# Node.net
KiCad netlist of a schematic drawn in EAGLE
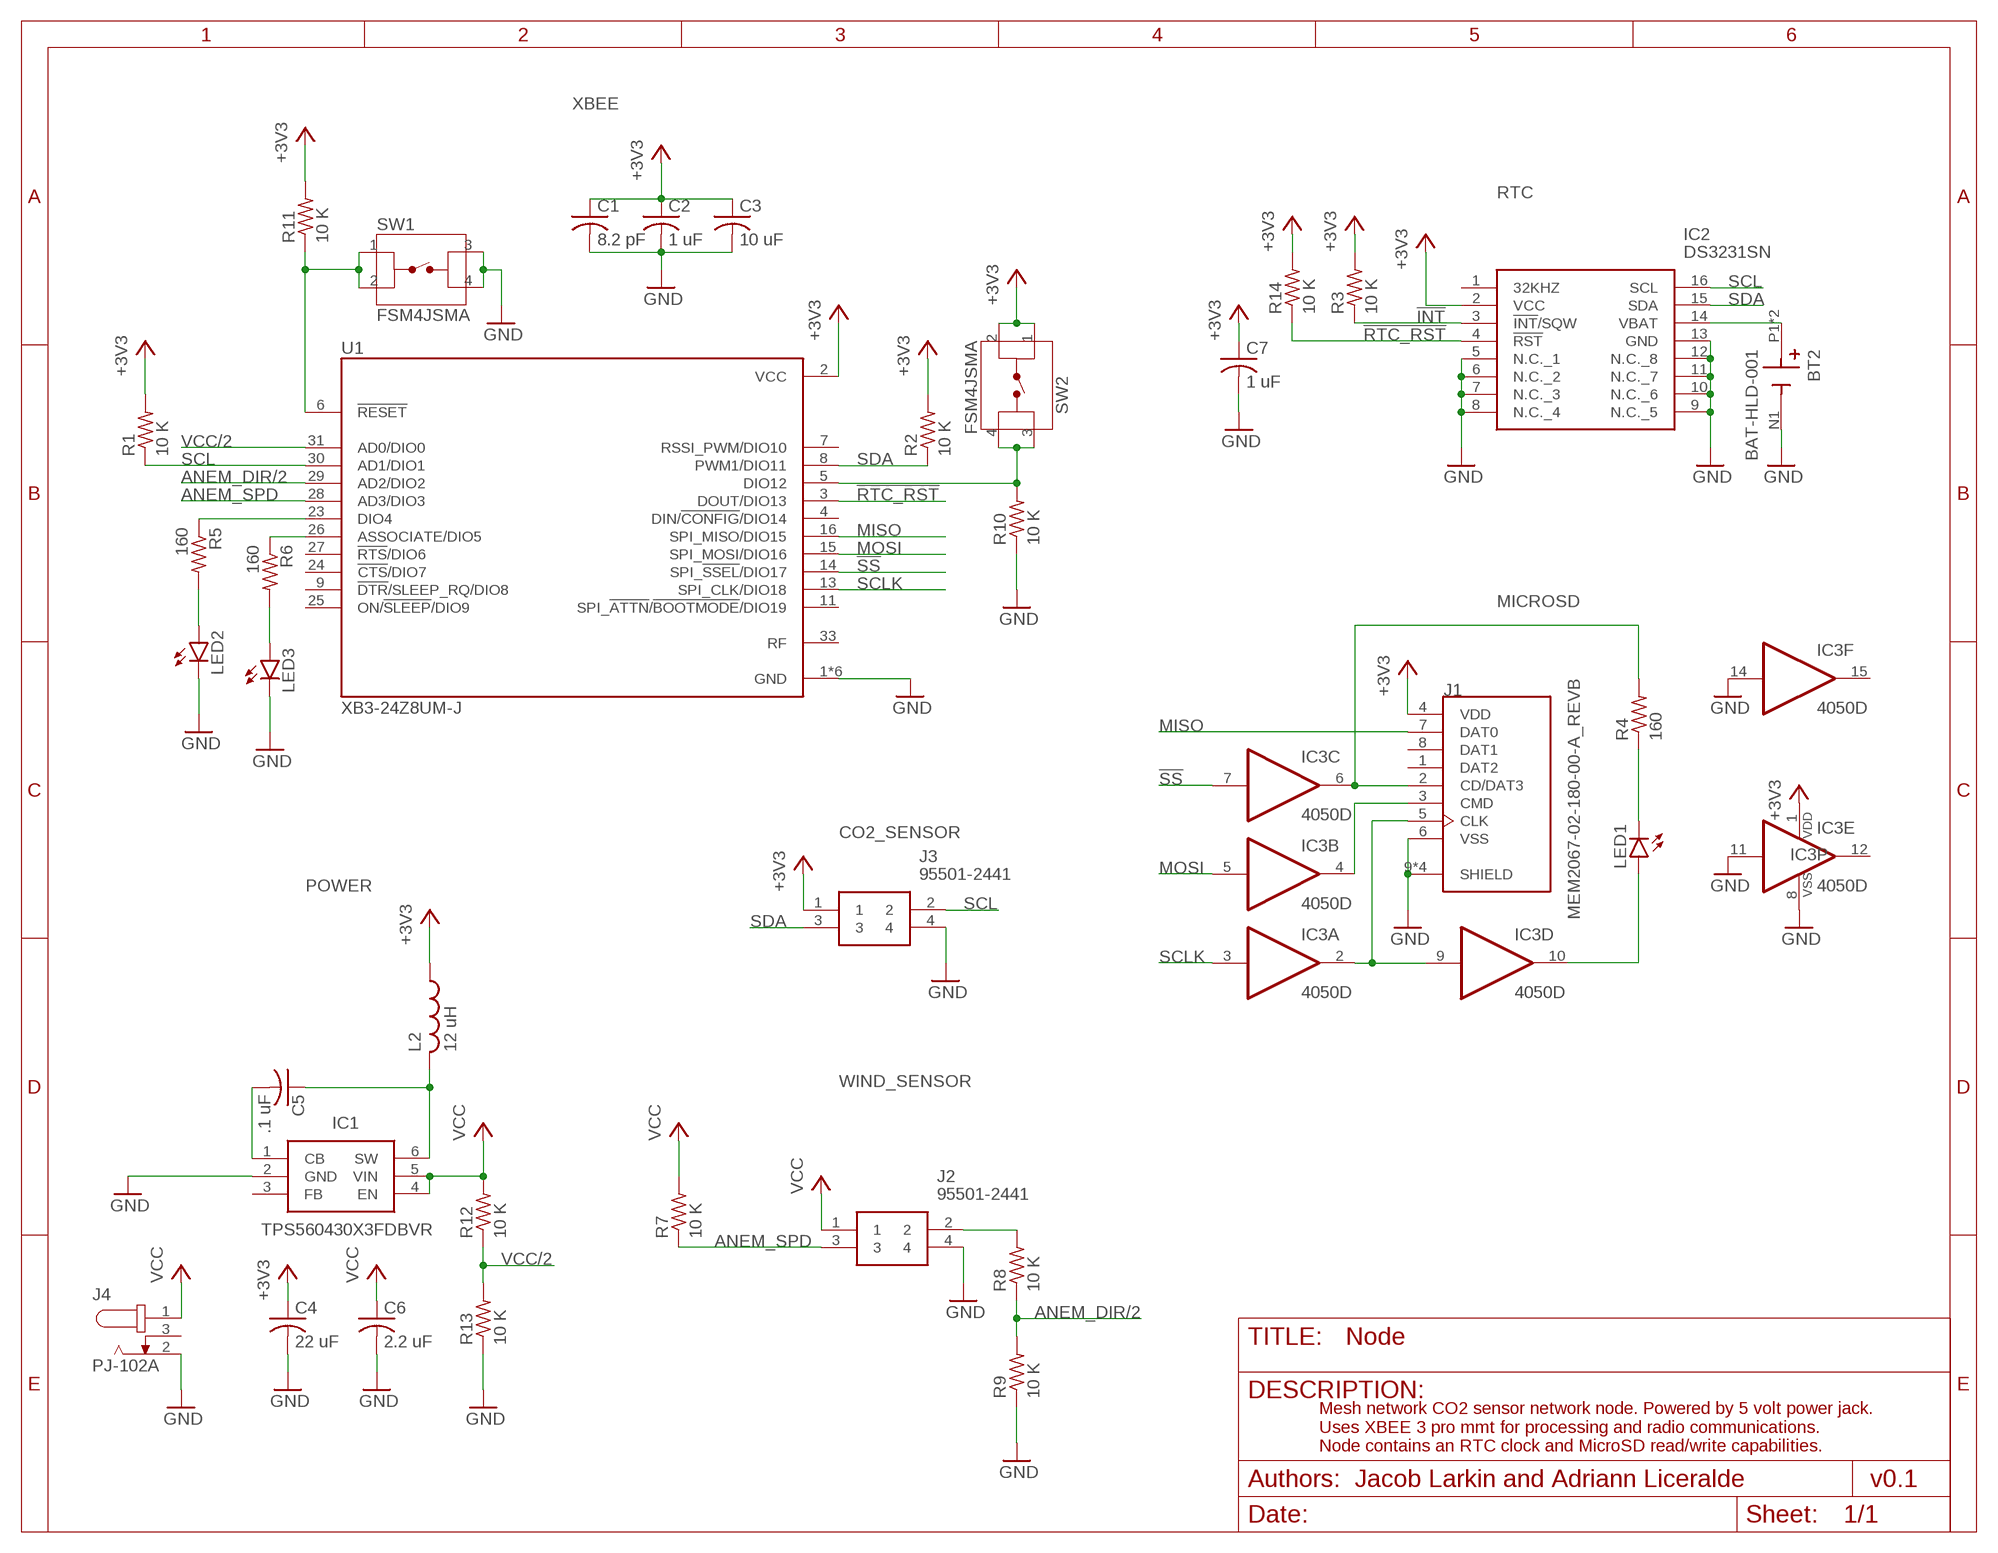
[diagram p0: schematic, sheet 1]

(export (version "E")
  (design (tool "Eeschema 10.0.6"))
  (components
    (comp (ref "BT2")
      (value "BAT-HLD-001")
      (footprint "eagle-import:BAT_BAT-HLD-001")
      (fields (field (name "MF") "Linx Technologies") (field (name "PRICE") ".29"))
      (libsource (lib "eagle-import") (part "BAT-HLD-001"))
    )
    (comp (ref "C1")
      (value "8.2 pF")
      (footprint "eagle-import:C0805")
      (libsource (lib "eagle-import") (part "C-USC0805"))
    )
    (comp (ref "C2")
      (value "1 uF")
      (footprint "eagle-import:C0805")
      (libsource (lib "eagle-import") (part "C-USC0805"))
    )
    (comp (ref "C3")
      (value "10 uF")
      (footprint "eagle-import:C0805")
      (libsource (lib "eagle-import") (part "C-USC0805"))
    )
    (comp (ref "C4")
      (value "22 uF")
      (footprint "eagle-import:C0805")
      (libsource (lib "eagle-import") (part "C-USC0805"))
    )
    (comp (ref "C5")
      (value ".1 uF")
      (footprint "eagle-import:C0805")
      (libsource (lib "eagle-import") (part "C-USC0805"))
    )
    (comp (ref "C6")
      (value "2.2 uF")
      (footprint "eagle-import:C0805")
      (libsource (lib "eagle-import") (part "C-USC0805"))
    )
    (comp (ref "C7")
      (value "1 uF")
      (footprint "eagle-import:C0805")
      (libsource (lib "eagle-import") (part "C-USC0805"))
    )
    (comp (ref "IC1")
      (value "TPS560430X3FDBVR")
      (footprint "eagle-import:SOT95P280X145-6N")
      (fields (field (name "MOUSER_PART_NUMBER") "595-TPS560430X3FDBVR"))
      (libsource (lib "eagle-import") (part "TPS560430X3FDBVR"))
    )
    (comp (ref "IC2")
      (value "DS3231SN")
      (footprint "eagle-import:SOIC127P1032X265-16N")
      (fields (field (name "MOUSER_PART_NUMBER") "700-DS3231SN"))
      (libsource (lib "eagle-import") (part "DS3231SN"))
    )
    (comp (ref "IC3")
      (value "4050D")
      (footprint "eagle-import:SO16")
      (fields
        (field (name "MOUSER_NUM") "771-74HC4050D-T")
        (field (name "PRICE") ".51")
        (field (name "PRICE_100") "25.70")
      )
      (libsource (lib "eagle-import") (part "4050D"))
    )
    (comp (ref "J1")
      (value "MEM2067-02-180-00-A_REVB")
      (footprint "eagle-import:GCT_MEM2067-02-180-00-A_REVB")
      (fields
        (field (name "MF") "Global Connector Technology")
        (field (name "MP") "MEM2067-02-180-00-A")
        (field (name "PRICE") "1.08")
      )
      (libsource (lib "eagle-import") (part "MEM2067-02-180-00-A_REVB"))
    )
    (comp (ref "J2")
      (value "95501-2441")
      (footprint "eagle-import:955012441")
      (fields (field (name "MOUSER_PART_NUMBER") "538-95501-2441"))
      (libsource (lib "eagle-import") (part "95501-2441"))
    )
    (comp (ref "J3")
      (value "95501-2441")
      (footprint "eagle-import:955012441")
      (fields (field (name "MOUSER_PART_NUMBER") "538-95501-2441"))
      (libsource (lib "eagle-import") (part "95501-2441"))
    )
    (comp (ref "J4")
      (value "PJ-102A")
      (footprint "eagle-import:CUI_PJ-102A")
      (fields (field (name "MF") "CUI Devices") (field (name "PRICE") ".64"))
      (libsource (lib "eagle-import") (part "PJ-102A"))
    )
    (comp (ref "L2")
      (value "12 uH")
      (footprint "eagle-import:L1812")
      (libsource (lib "eagle-import") (part "L-USL1812"))
    )
    (comp (ref "LED1")
      (value "LEDCHIP-LED0805")
      (footprint "eagle-import:CHIP-LED0805")
      (libsource (lib "eagle-import") (part "LEDCHIP-LED0805"))
    )
    (comp (ref "LED2")
      (value "LEDCHIP-LED0805")
      (footprint "eagle-import:CHIP-LED0805")
      (libsource (lib "eagle-import") (part "LEDCHIP-LED0805"))
    )
    (comp (ref "LED3")
      (value "LEDCHIP-LED0805")
      (footprint "eagle-import:CHIP-LED0805")
      (libsource (lib "eagle-import") (part "LEDCHIP-LED0805"))
    )
    (comp (ref "R1")
      (value "10 K")
      (footprint "eagle-import:R0805")
      (libsource (lib "eagle-import") (part "R-US_R0805"))
    )
    (comp (ref "R2")
      (value "10 K")
      (footprint "eagle-import:R0805")
      (libsource (lib "eagle-import") (part "R-US_R0805"))
    )
    (comp (ref "R3")
      (value "10 K")
      (footprint "eagle-import:R0805")
      (libsource (lib "eagle-import") (part "R-US_R0805"))
    )
    (comp (ref "R4")
      (value "160")
      (footprint "eagle-import:R0805")
      (libsource (lib "eagle-import") (part "R-US_R0805"))
    )
    (comp (ref "R5")
      (value "160")
      (footprint "eagle-import:R0805")
      (libsource (lib "eagle-import") (part "R-US_R0805"))
    )
    (comp (ref "R6")
      (value "160")
      (footprint "eagle-import:R0805")
      (libsource (lib "eagle-import") (part "R-US_R0805"))
    )
    (comp (ref "R7")
      (value "10 K")
      (footprint "eagle-import:R0805")
      (libsource (lib "eagle-import") (part "R-US_R0805"))
    )
    (comp (ref "R8")
      (value "10 K")
      (footprint "eagle-import:R0805")
      (libsource (lib "eagle-import") (part "R-US_R0805"))
    )
    (comp (ref "R9")
      (value "10 K")
      (footprint "eagle-import:R0805")
      (libsource (lib "eagle-import") (part "R-US_R0805"))
    )
    (comp (ref "R10")
      (value "10 K")
      (footprint "eagle-import:R0805")
      (libsource (lib "eagle-import") (part "R-US_R0805"))
    )
    (comp (ref "R11")
      (value "10 K")
      (footprint "eagle-import:R0805")
      (libsource (lib "eagle-import") (part "R-US_R0805"))
    )
    (comp (ref "R12")
      (value "10 K")
      (footprint "eagle-import:R0805")
      (libsource (lib "eagle-import") (part "R-US_R0805"))
    )
    (comp (ref "R13")
      (value "10 K")
      (footprint "eagle-import:R0805")
      (libsource (lib "eagle-import") (part "R-US_R0805"))
    )
    (comp (ref "R14")
      (value "10 K")
      (footprint "eagle-import:R0805")
      (libsource (lib "eagle-import") (part "R-US_R0805"))
    )
    (comp (ref "SW1")
      (value "FSM4JSMA")
      (footprint "eagle-import:FSM4JSMA")
      (fields
        (field (name "DIGIKEY_PART_NUMBER") "450-1129-ND")
        (field (name "MANUFACTURER") "TE Connectivity ALCOSWITCH Switches")
        (field (name "CREATED_BY") "PCBLayout.com")
      )
      (libsource (lib "eagle-import") (part "FSM4JSMA"))
    )
    (comp (ref "SW2")
      (value "FSM4JSMA")
      (footprint "eagle-import:FSM4JSMA")
      (fields
        (field (name "DIGIKEY_PART_NUMBER") "450-1129-ND")
        (field (name "MANUFACTURER") "TE Connectivity ALCOSWITCH Switches")
        (field (name "CREATED_BY") "PCBLayout.com")
      )
      (libsource (lib "eagle-import") (part "FSM4JSMA"))
    )
    (comp (ref "U1")
      (value "XB3-24Z8UM-J")
      (footprint "eagle-import:XCVR_XB3-24Z8UM-J")
      (fields (field (name "MF") "Digi International") (field (name "PRICE") "18.99"))
      (libsource (lib "eagle-import") (part "XB3-24Z8UM-J"))
    )
  )
  (nets
    (net (code "1") (name "+3V3") (class "Default")
      (node (ref "C1") (pin "1") (pinfunction "1_1") (pintype "passive"))
      (node (ref "C2") (pin "1") (pinfunction "1_1") (pintype "passive"))
      (node (ref "C3") (pin "1") (pinfunction "1_1") (pintype "passive"))
      (node (ref "C4") (pin "1") (pinfunction "1_1") (pintype "passive"))
      (node (ref "C7") (pin "1") (pinfunction "1_1") (pintype "passive"))
      (node (ref "IC2") (pin "2") (pinfunction "VCC_2") (pintype "bidirectional"))
      (node (ref "IC3") (pin "1") (pinfunction "VDD_1") (pintype "power_in"))
      (node (ref "J1") (pin "4") (pinfunction "VDD_4") (pintype "power_in"))
      (node (ref "J3") (pin "1") (pinfunction "1_1") (pintype "bidirectional"))
      (node (ref "L2") (pin "1") (pinfunction "1_1") (pintype "passive"))
      (node (ref "R1") (pin "2") (pinfunction "2_2") (pintype "passive"))
      (node (ref "R11") (pin "2") (pinfunction "2_2") (pintype "passive"))
      (node (ref "R14") (pin "2") (pinfunction "2_2") (pintype "passive"))
      (node (ref "R2") (pin "2") (pinfunction "2_2") (pintype "passive"))
      (node (ref "R3") (pin "2") (pinfunction "2_2") (pintype "passive"))
      (node (ref "SW2") (pin "1") (pinfunction "1_1") (pintype "passive"))
      (node (ref "SW2") (pin "2") (pinfunction "2_2") (pintype "passive"))
      (node (ref "U1") (pin "2") (pinfunction "VCC_2") (pintype "power_in"))
    )
    (net (code "2") (name "/ANEM_DIR{slash}2") (class "Default")
      (node (ref "R8") (pin "1") (pinfunction "1_1") (pintype "passive"))
      (node (ref "R9") (pin "2") (pinfunction "2_2") (pintype "passive"))
      (node (ref "U1") (pin "29") (pinfunction "AD2/DIO2_29") (pintype "bidirectional"))
    )
    (net (code "3") (name "/ANEM_SPD") (class "Default")
      (node (ref "J2") (pin "3") (pinfunction "3_3") (pintype "bidirectional"))
      (node (ref "R7") (pin "1") (pinfunction "1_1") (pintype "passive"))
      (node (ref "U1") (pin "28") (pinfunction "AD3/DIO3_28") (pintype "bidirectional"))
    )
    (net (code "4") (name "/MISO") (class "Default")
      (node (ref "J1") (pin "7") (pinfunction "DAT0_7") (pintype "bidirectional"))
      (node (ref "U1") (pin "16") (pinfunction "SPI_MISO/DIO15_16") (pintype "bidirectional"))
    )
    (net (code "5") (name "/MOSI") (class "Default")
      (node (ref "IC3") (pin "5") (pinfunction "I_5") (pintype "input"))
      (node (ref "U1") (pin "15") (pinfunction "SPI_MOSI/DIO16_15") (pintype "bidirectional"))
    )
    (net (code "6") (name "/SCL") (class "Default")
      (node (ref "IC2") (pin "16") (pinfunction "SCL_16") (pintype "bidirectional"))
      (node (ref "J3") (pin "2") (pinfunction "2_2") (pintype "bidirectional"))
      (node (ref "R1") (pin "1") (pinfunction "1_1") (pintype "passive"))
      (node (ref "U1") (pin "30") (pinfunction "AD1/DIO1_30") (pintype "bidirectional"))
    )
    (net (code "7") (name "/SCLK") (class "Default")
      (node (ref "IC3") (pin "3") (pinfunction "I_3") (pintype "input"))
      (node (ref "U1") (pin "13") (pinfunction "SPI_CLK/DIO18_13") (pintype "bidirectional"))
    )
    (net (code "8") (name "/SDA") (class "Default")
      (node (ref "IC2") (pin "15") (pinfunction "SDA_15") (pintype "bidirectional"))
      (node (ref "J3") (pin "3") (pinfunction "3_3") (pintype "bidirectional"))
      (node (ref "R2") (pin "1") (pinfunction "1_1") (pintype "passive"))
      (node (ref "U1") (pin "8") (pinfunction "PWM1/DIO11_8") (pintype "bidirectional"))
    )
    (net (code "9") (name "/VCC{slash}2") (class "Default")
      (node (ref "R12") (pin "1") (pinfunction "1_1") (pintype "passive"))
      (node (ref "R13") (pin "2") (pinfunction "2_2") (pintype "passive"))
      (node (ref "U1") (pin "31") (pinfunction "AD0/DIO0_31") (pintype "bidirectional"))
    )
    (net (code "10") (name "/~{INT}") (class "Default")
      (node (ref "IC2") (pin "3") (pinfunction "~{INT}/SQW_3") (pintype "bidirectional"))
      (node (ref "R3") (pin "1") (pinfunction "1_1") (pintype "passive"))
    )
    (net (code "11") (name "/~{RTC_RST}") (class "Default")
      (node (ref "IC2") (pin "4") (pinfunction "~{RST}_4") (pintype "bidirectional"))
      (node (ref "R14") (pin "1") (pinfunction "1_1") (pintype "passive"))
      (node (ref "U1") (pin "3") (pinfunction "DOUT/DIO13_3") (pintype "bidirectional"))
    )
    (net (code "12") (name "/~{SS}") (class "Default")
      (node (ref "IC3") (pin "7") (pinfunction "I_7") (pintype "input"))
      (node (ref "U1") (pin "14") (pinfunction "SPI_~{SSEL}/DIO17_14") (pintype "bidirectional"))
    )
    (net (code "13") (name "GND") (class "Default")
      (node (ref "BT2") (pin "N1") (pinfunction "-_N1") (pintype "passive"))
      (node (ref "C1") (pin "2") (pinfunction "2_2") (pintype "passive"))
      (node (ref "C2") (pin "2") (pinfunction "2_2") (pintype "passive"))
      (node (ref "C3") (pin "2") (pinfunction "2_2") (pintype "passive"))
      (node (ref "C4") (pin "2") (pinfunction "2_2") (pintype "passive"))
      (node (ref "C6") (pin "2") (pinfunction "2_2") (pintype "passive"))
      (node (ref "C7") (pin "2") (pinfunction "2_2") (pintype "passive"))
      (node (ref "IC1") (pin "2") (pinfunction "GND_2") (pintype "bidirectional"))
      (node (ref "IC2") (pin "10") (pinfunction "N.C._6_10") (pintype "bidirectional"))
      (node (ref "IC2") (pin "11") (pinfunction "N.C._7_11") (pintype "bidirectional"))
      (node (ref "IC2") (pin "12") (pinfunction "N.C._8_12") (pintype "bidirectional"))
      (node (ref "IC2") (pin "13") (pinfunction "GND_13") (pintype "bidirectional"))
      (node (ref "IC2") (pin "5") (pinfunction "N.C._1_5") (pintype "bidirectional"))
      (node (ref "IC2") (pin "6") (pinfunction "N.C._2_6") (pintype "bidirectional"))
      (node (ref "IC2") (pin "7") (pinfunction "N.C._3_7") (pintype "bidirectional"))
      (node (ref "IC2") (pin "8") (pinfunction "N.C._4_8") (pintype "bidirectional"))
      (node (ref "IC2") (pin "9") (pinfunction "N.C._5_9") (pintype "bidirectional"))
      (node (ref "IC3") (pin "11") (pinfunction "I_11") (pintype "input"))
      (node (ref "IC3") (pin "14") (pinfunction "I_14") (pintype "input"))
      (node (ref "IC3") (pin "8") (pinfunction "VSS_8") (pintype "power_in"))
      (node (ref "J1") (pin "10") (pinfunction "SHIELD_10") (pintype "passive"))
      (node (ref "J1") (pin "11") (pinfunction "SHIELD_11") (pintype "passive"))
      (node (ref "J1") (pin "12") (pinfunction "SHIELD_12") (pintype "passive"))
      (node (ref "J1") (pin "6") (pinfunction "VSS_6") (pintype "power_in"))
      (node (ref "J1") (pin "9") (pinfunction "SHIELD_9") (pintype "passive"))
      (node (ref "J2") (pin "4") (pinfunction "4_4") (pintype "bidirectional"))
      (node (ref "J3") (pin "4") (pinfunction "4_4") (pintype "bidirectional"))
      (node (ref "J4") (pin "2") (pinfunction "2_2") (pintype "passive"))
      (node (ref "LED2") (pin "C") (pinfunction "C_C") (pintype "passive"))
      (node (ref "LED3") (pin "C") (pinfunction "C_C") (pintype "passive"))
      (node (ref "R10") (pin "1") (pinfunction "1_1") (pintype "passive"))
      (node (ref "R13") (pin "1") (pinfunction "1_1") (pintype "passive"))
      (node (ref "R9") (pin "1") (pinfunction "1_1") (pintype "passive"))
      (node (ref "SW1") (pin "3") (pinfunction "3_3") (pintype "passive"))
      (node (ref "SW1") (pin "4") (pinfunction "4_4") (pintype "passive"))
      (node (ref "U1") (pin "1") (pinfunction "GND_1") (pintype "power_in"))
      (node (ref "U1") (pin "10") (pinfunction "GND_10") (pintype "power_in"))
      (node (ref "U1") (pin "12") (pinfunction "GND_12") (pintype "power_in"))
      (node (ref "U1") (pin "21") (pinfunction "GND_21") (pintype "power_in"))
      (node (ref "U1") (pin "32") (pinfunction "GND_32") (pintype "power_in"))
      (node (ref "U1") (pin "34") (pinfunction "GND_34") (pintype "power_in"))
    )
    (net (code "14") (name "Net-(IC1-CB)") (class "Default")
      (node (ref "C5") (pin "2") (pinfunction "2_2") (pintype "passive"))
      (node (ref "IC1") (pin "1") (pinfunction "CB_1") (pintype "bidirectional"))
    )
    (net (code "15") (name "Net-(IC1-SW)") (class "Default")
      (node (ref "C5") (pin "1") (pinfunction "1_1") (pintype "passive"))
      (node (ref "IC1") (pin "6") (pinfunction "SW_6") (pintype "bidirectional"))
      (node (ref "L2") (pin "2") (pinfunction "2_2") (pintype "passive"))
    )
    (net (code "16") (name "Net-(IC2-VBAT)") (class "Default")
      (node (ref "BT2") (pin "P1") (pinfunction "+_P1") (pintype "passive"))
      (node (ref "BT2") (pin "P2") (pinfunction "+_P2") (pintype "passive"))
      (node (ref "IC2") (pin "14") (pinfunction "VBAT_14") (pintype "bidirectional"))
    )
    (net (code "17") (name "Net-(IC3A-O)") (class "Default")
      (node (ref "IC3") (pin "2") (pinfunction "O_2") (pintype "output"))
      (node (ref "IC3") (pin "9") (pinfunction "I_9") (pintype "input"))
      (node (ref "J1") (pin "5") (pinfunction "CLK_5") (pintype "bidirectional"))
    )
    (net (code "18") (name "Net-(IC3B-O)") (class "Default")
      (node (ref "IC3") (pin "4") (pinfunction "O_4") (pintype "output"))
      (node (ref "J1") (pin "3") (pinfunction "CMD_3") (pintype "bidirectional"))
    )
    (net (code "19") (name "Net-(IC3C-O)") (class "Default")
      (node (ref "IC3") (pin "6") (pinfunction "O_6") (pintype "output"))
      (node (ref "J1") (pin "2") (pinfunction "CD/DAT3_2") (pintype "bidirectional"))
      (node (ref "R4") (pin "2") (pinfunction "2_2") (pintype "passive"))
    )
    (net (code "20") (name "Net-(IC3D-O)") (class "Default")
      (node (ref "IC3") (pin "10") (pinfunction "O_10") (pintype "output"))
      (node (ref "LED1") (pin "A") (pinfunction "A_A") (pintype "passive"))
    )
    (net (code "21") (name "Net-(J2-Pad2)") (class "Default")
      (node (ref "J2") (pin "2") (pinfunction "2_2") (pintype "bidirectional"))
      (node (ref "R8") (pin "2") (pinfunction "2_2") (pintype "passive"))
    )
    (net (code "22") (name "Net-(LED1-PadC)") (class "Default")
      (node (ref "LED1") (pin "C") (pinfunction "C_C") (pintype "passive"))
      (node (ref "R4") (pin "1") (pinfunction "1_1") (pintype "passive"))
    )
    (net (code "23") (name "Net-(LED2-PadA)") (class "Default")
      (node (ref "LED2") (pin "A") (pinfunction "A_A") (pintype "passive"))
      (node (ref "R5") (pin "2") (pinfunction "2_2") (pintype "passive"))
    )
    (net (code "24") (name "Net-(LED3-PadA)") (class "Default")
      (node (ref "LED3") (pin "A") (pinfunction "A_A") (pintype "passive"))
      (node (ref "R6") (pin "2") (pinfunction "2_2") (pintype "passive"))
    )
    (net (code "25") (name "Net-(U1-ASSOCIATE{slash}DIO5)") (class "Default")
      (node (ref "R6") (pin "1") (pinfunction "1_1") (pintype "passive"))
      (node (ref "U1") (pin "26") (pinfunction "ASSOCIATE/DIO5_26") (pintype "bidirectional"))
    )
    (net (code "26") (name "Net-(U1-DIO4)") (class "Default")
      (node (ref "R5") (pin "1") (pinfunction "1_1") (pintype "passive"))
      (node (ref "U1") (pin "23") (pinfunction "DIO4_23") (pintype "bidirectional"))
    )
    (net (code "27") (name "Net-(U1-DIO12)") (class "Default")
      (node (ref "R10") (pin "2") (pinfunction "2_2") (pintype "passive"))
      (node (ref "SW2") (pin "3") (pinfunction "3_3") (pintype "passive"))
      (node (ref "SW2") (pin "4") (pinfunction "4_4") (pintype "passive"))
      (node (ref "U1") (pin "5") (pinfunction "DIO12_5") (pintype "bidirectional"))
    )
    (net (code "28") (name "Net-(U1-~{RESET})") (class "Default")
      (node (ref "R11") (pin "1") (pinfunction "1_1") (pintype "passive"))
      (node (ref "SW1") (pin "1") (pinfunction "1_1") (pintype "passive"))
      (node (ref "SW1") (pin "2") (pinfunction "2_2") (pintype "passive"))
      (node (ref "U1") (pin "6") (pinfunction "~{RESET}_6") (pintype "input"))
    )
    (net (code "29") (name "VCC") (class "Default")
      (node (ref "C6") (pin "1") (pinfunction "1_1") (pintype "passive"))
      (node (ref "IC1") (pin "4") (pinfunction "EN_4") (pintype "bidirectional"))
      (node (ref "IC1") (pin "5") (pinfunction "VIN_5") (pintype "bidirectional"))
      (node (ref "J2") (pin "1") (pinfunction "1_1") (pintype "bidirectional"))
      (node (ref "J4") (pin "1") (pinfunction "1_1") (pintype "passive"))
      (node (ref "R12") (pin "2") (pinfunction "2_2") (pintype "passive"))
      (node (ref "R7") (pin "2") (pinfunction "2_2") (pintype "passive"))
    )
    (net (code "30") (name "unconnected-(IC1-FB-Pad3)") (class "Default")
      (node (ref "IC1") (pin "3") (pinfunction "FB_3") (pintype "bidirectional"))
    )
    (net (code "31") (name "unconnected-(IC2-32KHZ-Pad1)") (class "Default")
      (node (ref "IC2") (pin "1") (pinfunction "32KHZ_1") (pintype "bidirectional"))
    )
    (net (code "32") (name "unconnected-(IC3E-O-Pad12)") (class "Default")
      (node (ref "IC3") (pin "12") (pinfunction "O_12") (pintype "output"))
    )
    (net (code "33") (name "unconnected-(IC3F-O-Pad15)") (class "Default")
      (node (ref "IC3") (pin "15") (pinfunction "O_15") (pintype "output"))
    )
    (net (code "34") (name "unconnected-(J1-DAT1-Pad8)") (class "Default")
      (node (ref "J1") (pin "8") (pinfunction "DAT1_8") (pintype "bidirectional"))
    )
    (net (code "35") (name "unconnected-(J1-DAT2-Pad1)") (class "Default")
      (node (ref "J1") (pin "1") (pinfunction "DAT2_1") (pintype "bidirectional"))
    )
    (net (code "36") (name "unconnected-(J4-Pad3)") (class "Default")
      (node (ref "J4") (pin "3") (pinfunction "3_3") (pintype "passive"))
    )
    (net (code "37") (name "unconnected-(U1-DIN{slash}~{CONFIG}{slash}DIO14-Pad4)") (class "Default")
      (node (ref "U1") (pin "4") (pinfunction "DIN/~{CONFIG}/DIO14_4") (pintype "bidirectional"))
    )
    (net (code "38") (name "unconnected-(U1-ON{slash}~{SLEEP}{slash}DIO9-Pad25)") (class "Default")
      (node (ref "U1") (pin "25") (pinfunction "ON/~{SLEEP}/DIO9_25") (pintype "bidirectional"))
    )
    (net (code "39") (name "unconnected-(U1-RF-Pad33)") (class "Default")
      (node (ref "U1") (pin "33") (pinfunction "RF_33") (pintype "bidirectional"))
    )
    (net (code "40") (name "unconnected-(U1-RSSI_PWM{slash}DIO10-Pad7)") (class "Default")
      (node (ref "U1") (pin "7") (pinfunction "RSSI_PWM/DIO10_7") (pintype "bidirectional"))
    )
    (net (code "41") (name "unconnected-(U1-SPI_~{ATTN}{slash}~{BOOTMODE}{slash}DIO19-Pad11)") (class "Default")
      (node (ref "U1") (pin "11") (pinfunction "SPI_~{ATTN}/~{BOOTMODE}/DIO19_11") (pintype "bidirectional"))
    )
    (net (code "42") (name "unconnected-(U1-~{CTS}{slash}DIO7-Pad24)") (class "Default")
      (node (ref "U1") (pin "24") (pinfunction "~{CTS}/DIO7_24") (pintype "bidirectional"))
    )
    (net (code "43") (name "unconnected-(U1-~{DTR}{slash}SLEEP_RQ{slash}DIO8-Pad9)") (class "Default")
      (node (ref "U1") (pin "9") (pinfunction "~{DTR}/SLEEP_RQ/DIO8_9") (pintype "bidirectional"))
    )
    (net (code "44") (name "unconnected-(U1-~{RTS}{slash}DIO6-Pad27)") (class "Default")
      (node (ref "U1") (pin "27") (pinfunction "~{RTS}/DIO6_27") (pintype "bidirectional"))
    )
  )
)
